# pc_ads1292r_shield_v3_1.net
KiCad netlist of a schematic drawn in EAGLE
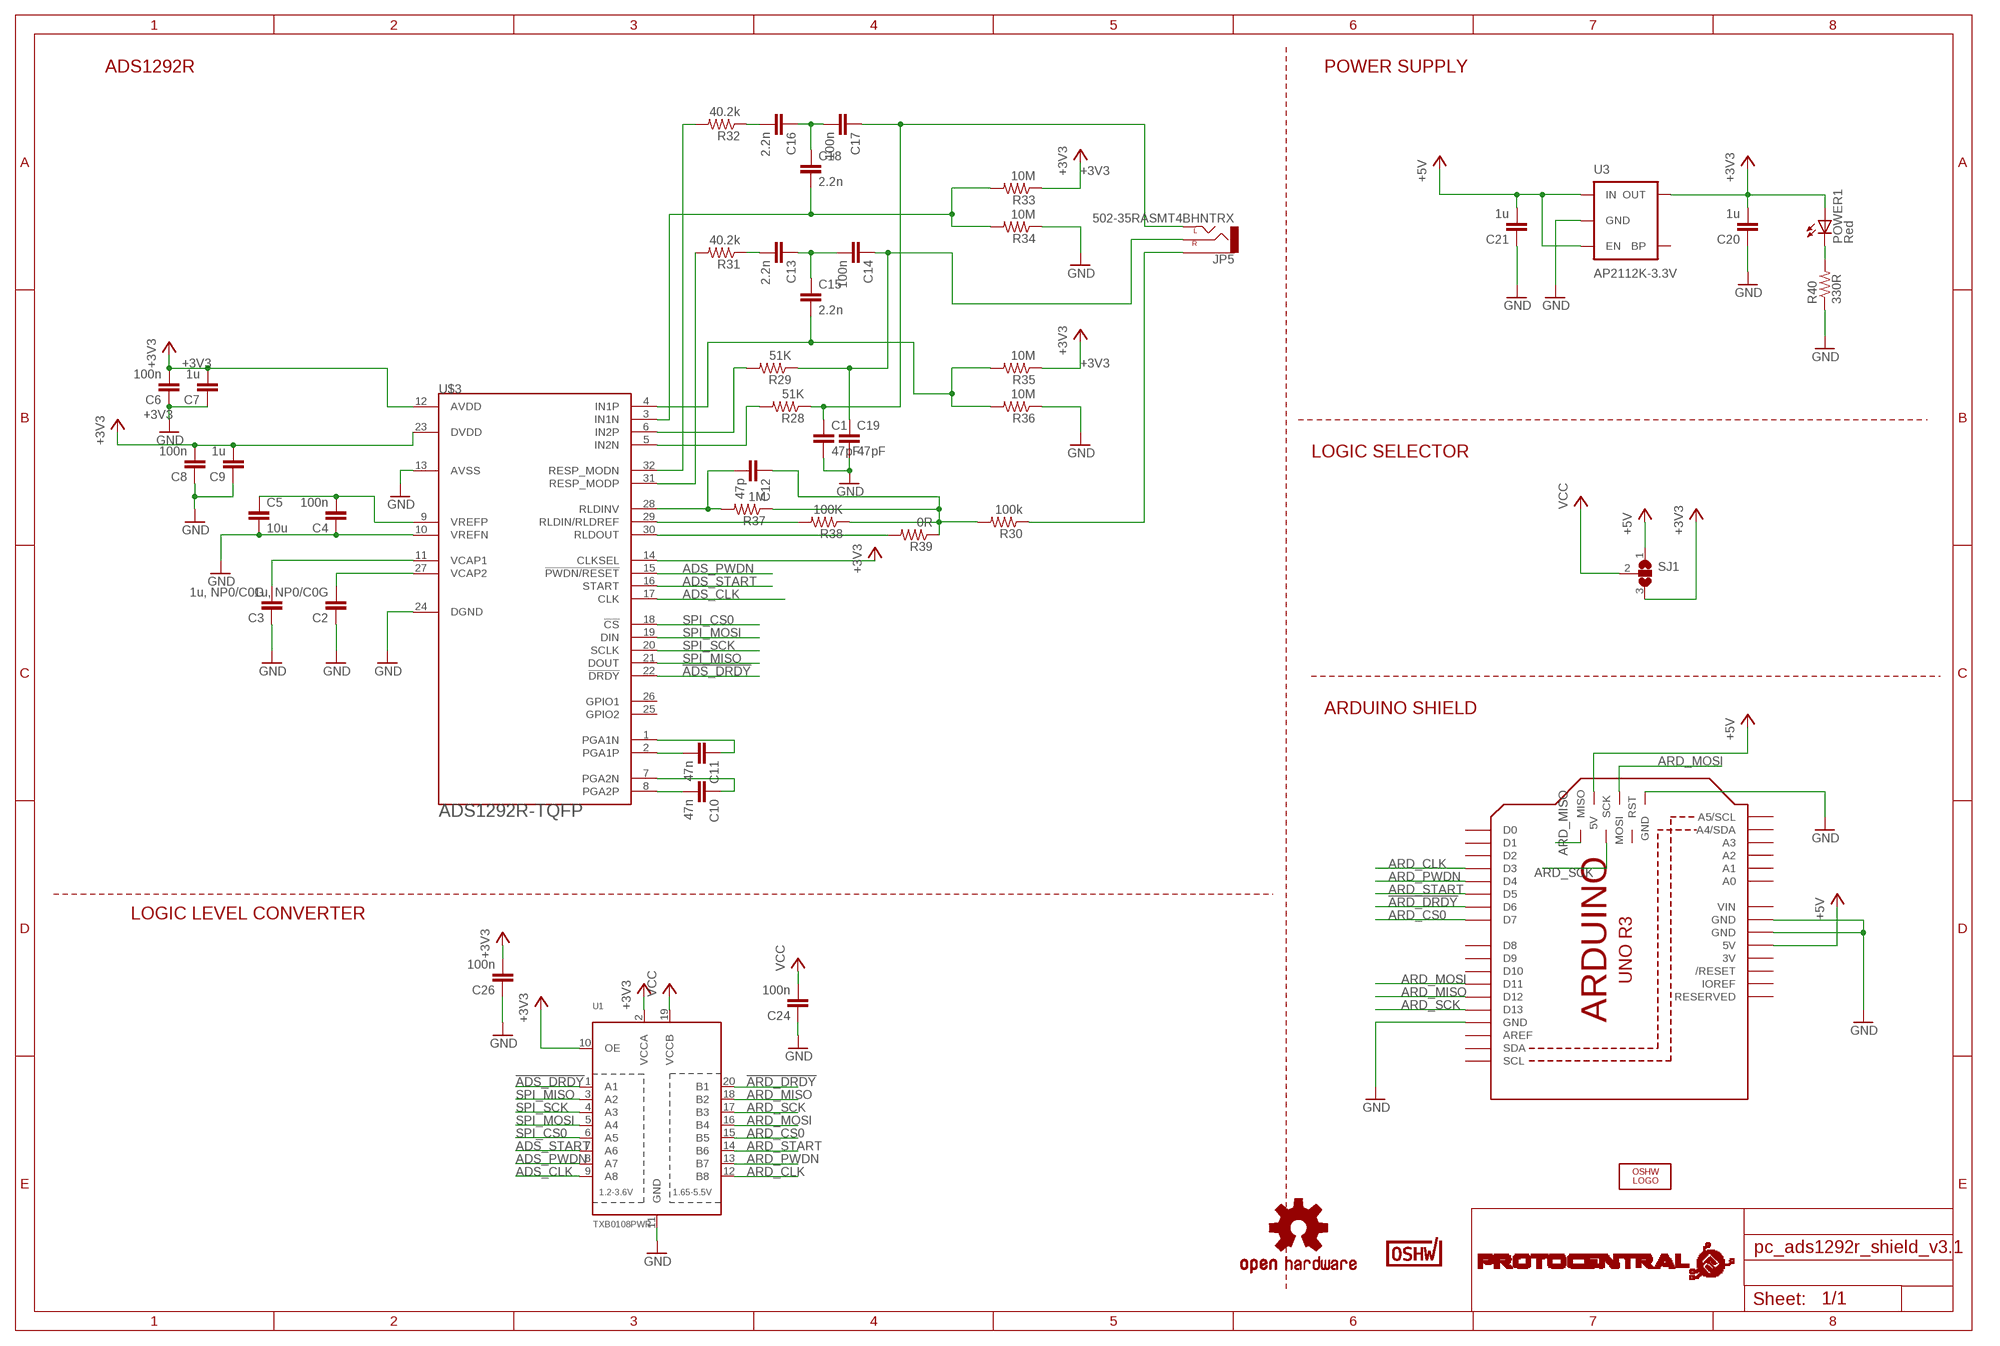
[diagram p0: schematic, sheet 1]

(export (version "E")
  (design (tool "Eeschema 10.0.6"))
  (components
    (comp (ref "C1")
      (value "47pF")
      (footprint "eagle-import:C0402")
      (libsource (lib "eagle-import") (part "C-EUC0402"))
    )
    (comp (ref "C2")
      (value "1u, NP0/C0G")
      (footprint "eagle-import:C0402")
      (libsource (lib "eagle-import") (part "C-EUC0402"))
    )
    (comp (ref "C3")
      (value "1u, NP0/C0G")
      (footprint "eagle-import:C0402")
      (libsource (lib "eagle-import") (part "C-EUC0402"))
    )
    (comp (ref "C4")
      (value "100n")
      (footprint "eagle-import:C0402")
      (libsource (lib "eagle-import") (part "C-EUC0402"))
    )
    (comp (ref "C5")
      (value "10u")
      (footprint "eagle-import:C0603")
      (libsource (lib "eagle-import") (part "resistor_C-EUC0603"))
    )
    (comp (ref "C6")
      (value "100n")
      (footprint "eagle-import:C0402")
      (libsource (lib "eagle-import") (part "C-EUC0402"))
    )
    (comp (ref "C7")
      (value "1u")
      (footprint "eagle-import:C0402")
      (libsource (lib "eagle-import") (part "C-EUC0402"))
    )
    (comp (ref "C8")
      (value "100n")
      (footprint "eagle-import:C0402")
      (libsource (lib "eagle-import") (part "C-EUC0402"))
    )
    (comp (ref "C9")
      (value "1u")
      (footprint "eagle-import:C0402")
      (libsource (lib "eagle-import") (part "C-EUC0402"))
    )
    (comp (ref "C10")
      (value "47n")
      (footprint "eagle-import:C0402")
      (libsource (lib "eagle-import") (part "C-EUC0402"))
    )
    (comp (ref "C11")
      (value "47n")
      (footprint "eagle-import:C0402")
      (libsource (lib "eagle-import") (part "C-EUC0402"))
    )
    (comp (ref "C12")
      (value "47p")
      (footprint "eagle-import:C0402")
      (libsource (lib "eagle-import") (part "C-EUC0402"))
    )
    (comp (ref "C13")
      (value "2.2n")
      (footprint "eagle-import:C0402")
      (libsource (lib "eagle-import") (part "C-EUC0402"))
    )
    (comp (ref "C14")
      (value "100n")
      (footprint "eagle-import:C0402")
      (libsource (lib "eagle-import") (part "C-EUC0402"))
    )
    (comp (ref "C15")
      (value "2.2n")
      (footprint "eagle-import:C0402")
      (libsource (lib "eagle-import") (part "C-EUC0402"))
    )
    (comp (ref "C16")
      (value "2.2n")
      (footprint "eagle-import:C0402")
      (libsource (lib "eagle-import") (part "C-EUC0402"))
    )
    (comp (ref "C17")
      (value "100n")
      (footprint "eagle-import:C0402")
      (libsource (lib "eagle-import") (part "C-EUC0402"))
    )
    (comp (ref "C18")
      (value "2.2n")
      (footprint "eagle-import:C0402")
      (libsource (lib "eagle-import") (part "C-EUC0402"))
    )
    (comp (ref "C19")
      (value "47pF")
      (footprint "eagle-import:C0402")
      (libsource (lib "eagle-import") (part "C-EUC0402"))
    )
    (comp (ref "C20")
      (value "1u")
      (footprint "eagle-import:C0402")
      (libsource (lib "eagle-import") (part "C-EUC0402"))
    )
    (comp (ref "C21")
      (value "1u")
      (footprint "eagle-import:C0402")
      (libsource (lib "eagle-import") (part "C-EUC0402"))
    )
    (comp (ref "C24")
      (value "100n")
      (footprint "eagle-import:C0402")
      (libsource (lib "eagle-import") (part "C-EUC0402"))
    )
    (comp (ref "C26")
      (value "100n")
      (footprint "eagle-import:C0402")
      (libsource (lib "eagle-import") (part "C-EUC0402"))
    )
    (comp (ref "JP5")
      (value "502-35RASMT4BHNTRX")
      (footprint "eagle-import:AUDIO-JACK-3.5MM-SMD")
      (libsource (lib "eagle-import") (part "AUDIO-JACKSMD2"))
    )
    (comp (ref "LOGO1")
      (value "OSHW_LOGO_FILLX0100-NT")
      (footprint "eagle-import:OSHW_FILLX100_NOTEXT")
      (libsource (lib "eagle-import") (part "OSHW_LOGO_FILLX0100-NT"))
    )
    (comp (ref "M1")
      (value "ARDUINO")
      (footprint "eagle-import:ARDUINO")
      (libsource (lib "eagle-import") (part "ARDUINO"))
    )
    (comp (ref "POWER1")
      (value "Red")
      (footprint "eagle-import:CHIPLED_0603")
      (libsource (lib "eagle-import") (part "LEDCHIPLED_0603"))
    )
    (comp (ref "R28")
      (value "51K")
      (footprint "eagle-import:R0402")
      (libsource (lib "eagle-import") (part "R-US_R0402"))
    )
    (comp (ref "R29")
      (value "51K")
      (footprint "eagle-import:R0402")
      (libsource (lib "eagle-import") (part "R-US_R0402"))
    )
    (comp (ref "R30")
      (value "100k")
      (footprint "eagle-import:R0402")
      (libsource (lib "eagle-import") (part "R-US_R0402"))
    )
    (comp (ref "R31")
      (value "40.2k")
      (footprint "eagle-import:R0402")
      (libsource (lib "eagle-import") (part "R-US_R0402"))
    )
    (comp (ref "R32")
      (value "40.2k")
      (footprint "eagle-import:R0402")
      (libsource (lib "eagle-import") (part "R-US_R0402"))
    )
    (comp (ref "R33")
      (value "10M")
      (footprint "eagle-import:R0402")
      (libsource (lib "eagle-import") (part "R-US_R0402"))
    )
    (comp (ref "R34")
      (value "10M")
      (footprint "eagle-import:R0402")
      (libsource (lib "eagle-import") (part "R-US_R0402"))
    )
    (comp (ref "R35")
      (value "10M")
      (footprint "eagle-import:R0402")
      (libsource (lib "eagle-import") (part "R-US_R0402"))
    )
    (comp (ref "R36")
      (value "10M")
      (footprint "eagle-import:R0402")
      (libsource (lib "eagle-import") (part "R-US_R0402"))
    )
    (comp (ref "R37")
      (value "1M")
      (footprint "eagle-import:R0402")
      (libsource (lib "eagle-import") (part "R-US_R0402"))
    )
    (comp (ref "R38")
      (value "100K")
      (footprint "eagle-import:R0402")
      (libsource (lib "eagle-import") (part "R-US_R0402"))
    )
    (comp (ref "R39")
      (value "0R")
      (footprint "eagle-import:R0402")
      (libsource (lib "eagle-import") (part "R-US_R0402"))
    )
    (comp (ref "R40")
      (value "330R")
      (footprint "eagle-import:R0402")
      (libsource (lib "eagle-import") (part "R-US_R0402"))
    )
    (comp (ref "SJ1")
      (value "SJ2W")
      (footprint "eagle-import:SJ_2")
      (libsource (lib "eagle-import") (part "SJ2W"))
    )
    (comp (ref "U$1")
      (value "CERT-SMALL")
      (footprint "eagle-import:CERT-SMALL-SILK")
      (libsource (lib "eagle-import") (part "CERT-SMALL"))
    )
    (comp (ref "U$3")
      (value "ADS1292R-TQFP")
      (footprint "eagle-import:SQFP-S-5X5-32")
      (libsource (lib "eagle-import") (part "ADS1292R-TQFP"))
    )
    (comp (ref "U$4")
      (value "PROTY_LOGO_WITH_TEXT")
      (footprint "eagle-import:PROTY_WITH_TEXT")
      (libsource (lib "eagle-import") (part "PROTY_LOGO_WITH_TEXT"))
    )
    (comp (ref "U$6")
      (value "OSHW-LOGOS")
      (footprint "eagle-import:OSHW-LOGO-S")
      (libsource (lib "eagle-import") (part "OSHW-LOGOS"))
    )
    (comp (ref "U1")
      (value "TXB0108PWR")
      (footprint "eagle-import:TSSOP20")
      (libsource (lib "eagle-import") (part "TXB0108PWR"))
    )
    (comp (ref "U3")
      (value "AP2112K-3.3V")
      (footprint "eagle-import:SOT23-5")
      (libsource (lib "eagle-import") (part "V_REG_LDOSMD"))
    )
  )
  (nets
    (net (code "1") (name "+3V3") (class "Default")
      (node (ref "C20") (pin "2") (pinfunction "2_2") (pintype "passive"))
      (node (ref "C26") (pin "2") (pinfunction "2_2") (pintype "passive"))
      (node (ref "C6") (pin "2") (pinfunction "2_2") (pintype "passive"))
      (node (ref "C7") (pin "2") (pinfunction "2_2") (pintype "passive"))
      (node (ref "C8") (pin "2") (pinfunction "2_2") (pintype "passive"))
      (node (ref "C9") (pin "2") (pinfunction "2_2") (pintype "passive"))
      (node (ref "POWER1") (pin "A") (pinfunction "A_A") (pintype "passive"))
      (node (ref "R33") (pin "1") (pinfunction "1_1") (pintype "passive"))
      (node (ref "R35") (pin "1") (pinfunction "1_1") (pintype "passive"))
      (node (ref "SJ1") (pin "3") (pinfunction "3_3") (pintype "passive"))
      (node (ref "U$3") (pin "12") (pinfunction "AVDD_12") (pintype "power_in"))
      (node (ref "U$3") (pin "14") (pinfunction "CLKSEL_14") (pintype "bidirectional"))
      (node (ref "U$3") (pin "23") (pinfunction "DVDD_23") (pintype "power_in"))
      (node (ref "U1") (pin "10") (pinfunction "OE_10") (pintype "bidirectional"))
      (node (ref "U1") (pin "2") (pinfunction "VCCA_2") (pintype "bidirectional"))
      (node (ref "U3") (pin "5") (pinfunction "OUT_5") (pintype "passive"))
    )
    (net (code "2") (name "+5V") (class "Default")
      (node (ref "C21") (pin "2") (pinfunction "2_2") (pintype "passive"))
      (node (ref "M1") (pin "5V") (pinfunction "5V_5V") (pintype "power_in"))
      (node (ref "M1") (pin "5V_ICSP") (pinfunction "5V_5V_ICSP") (pintype "passive"))
      (node (ref "SJ1") (pin "1") (pinfunction "1_1") (pintype "passive"))
      (node (ref "U3") (pin "1") (pinfunction "IN_1") (pintype "input"))
      (node (ref "U3") (pin "3") (pinfunction "EN_3") (pintype "input"))
    )
    (net (code "3") (name "/3V") (class "Default")
      (node (ref "M1") (pin "3V") (pinfunction "3V_3V") (pintype "power_in"))
    )
    (net (code "4") (name "/ADS_CLK") (class "Default")
      (node (ref "U$3") (pin "17") (pinfunction "CLK_17") (pintype "bidirectional"))
      (node (ref "U1") (pin "9") (pinfunction "A8_9") (pintype "bidirectional"))
    )
    (net (code "5") (name "/ADS_PWDN") (class "Default")
      (node (ref "U$3") (pin "15") (pinfunction "~{PWDN/RESET}_15") (pintype "bidirectional"))
      (node (ref "U1") (pin "8") (pinfunction "A7_8") (pintype "bidirectional"))
    )
    (net (code "6") (name "/ADS_START") (class "Default")
      (node (ref "U$3") (pin "16") (pinfunction "START_16") (pintype "bidirectional"))
      (node (ref "U1") (pin "7") (pinfunction "A6_7") (pintype "bidirectional"))
    )
    (net (code "7") (name "/ARD_CLK") (class "Default")
      (node (ref "M1") (pin "D3") (pinfunction "D3_D3") (pintype "bidirectional"))
      (node (ref "U1") (pin "12") (pinfunction "B8_12") (pintype "bidirectional"))
    )
    (net (code "8") (name "/ARD_CS0") (class "Default")
      (node (ref "M1") (pin "D7") (pinfunction "D7_D7") (pintype "bidirectional"))
      (node (ref "U1") (pin "15") (pinfunction "B5_15") (pintype "bidirectional"))
    )
    (net (code "9") (name "/ARD_MISO") (class "Default")
      (node (ref "M1") (pin "D12") (pinfunction "D12_D12") (pintype "bidirectional"))
      (node (ref "M1") (pin "MISO") (pinfunction "MISO_MISO") (pintype "passive"))
      (node (ref "U1") (pin "18") (pinfunction "B2_18") (pintype "bidirectional"))
    )
    (net (code "10") (name "/ARD_MOSI") (class "Default")
      (node (ref "M1") (pin "D11") (pinfunction "D11_D11") (pintype "bidirectional"))
      (node (ref "M1") (pin "MOSI") (pinfunction "MOSI_MOSI") (pintype "passive"))
      (node (ref "U1") (pin "16") (pinfunction "B4_16") (pintype "bidirectional"))
    )
    (net (code "11") (name "/ARD_PWDN") (class "Default")
      (node (ref "M1") (pin "D4") (pinfunction "D4_D4") (pintype "bidirectional"))
      (node (ref "U1") (pin "13") (pinfunction "B7_13") (pintype "bidirectional"))
    )
    (net (code "12") (name "/ARD_SCK") (class "Default")
      (node (ref "M1") (pin "D13") (pinfunction "D13_D13") (pintype "bidirectional"))
      (node (ref "M1") (pin "SCK") (pinfunction "SCK_SCK") (pintype "passive"))
      (node (ref "U1") (pin "17") (pinfunction "B3_17") (pintype "bidirectional"))
    )
    (net (code "13") (name "/ARD_START") (class "Default")
      (node (ref "M1") (pin "D5") (pinfunction "D5_D5") (pintype "bidirectional"))
      (node (ref "U1") (pin "14") (pinfunction "B6_14") (pintype "bidirectional"))
    )
    (net (code "14") (name "/SPI_CS0") (class "Default")
      (node (ref "U$3") (pin "18") (pinfunction "~{CS}_18") (pintype "bidirectional"))
      (node (ref "U1") (pin "6") (pinfunction "A5_6") (pintype "bidirectional"))
    )
    (net (code "15") (name "/SPI_MISO") (class "Default")
      (node (ref "U$3") (pin "21") (pinfunction "DOUT_21") (pintype "bidirectional"))
      (node (ref "U1") (pin "3") (pinfunction "A2_3") (pintype "bidirectional"))
    )
    (net (code "16") (name "/SPI_MOSI") (class "Default")
      (node (ref "U$3") (pin "19") (pinfunction "DIN_19") (pintype "bidirectional"))
      (node (ref "U1") (pin "5") (pinfunction "A4_5") (pintype "bidirectional"))
    )
    (net (code "17") (name "/SPI_SCK") (class "Default")
      (node (ref "U$3") (pin "20") (pinfunction "SCLK_20") (pintype "bidirectional"))
      (node (ref "U1") (pin "4") (pinfunction "A3_4") (pintype "bidirectional"))
    )
    (net (code "18") (name "/VIN") (class "Default")
      (node (ref "M1") (pin "VIN") (pinfunction "VIN_VIN") (pintype "power_in"))
    )
    (net (code "19") (name "/~{ADS_DRDY}") (class "Default")
      (node (ref "U$3") (pin "22") (pinfunction "~{DRDY}_22") (pintype "bidirectional"))
      (node (ref "U1") (pin "1") (pinfunction "A1_1") (pintype "bidirectional"))
    )
    (net (code "20") (name "/~{ARD_DRDY}") (class "Default")
      (node (ref "M1") (pin "D6") (pinfunction "D6_D6") (pintype "bidirectional"))
      (node (ref "U1") (pin "20") (pinfunction "B1_20") (pintype "bidirectional"))
    )
    (net (code "21") (name "GND") (class "Default")
      (node (ref "C1") (pin "2") (pinfunction "2_2") (pintype "passive"))
      (node (ref "C19") (pin "2") (pinfunction "2_2") (pintype "passive"))
      (node (ref "C2") (pin "1") (pinfunction "1_1") (pintype "passive"))
      (node (ref "C20") (pin "1") (pinfunction "1_1") (pintype "passive"))
      (node (ref "C21") (pin "1") (pinfunction "1_1") (pintype "passive"))
      (node (ref "C24") (pin "1") (pinfunction "1_1") (pintype "passive"))
      (node (ref "C26") (pin "1") (pinfunction "1_1") (pintype "passive"))
      (node (ref "C3") (pin "1") (pinfunction "1_1") (pintype "passive"))
      (node (ref "C4") (pin "1") (pinfunction "1_1") (pintype "passive"))
      (node (ref "C5") (pin "2") (pinfunction "2_2") (pintype "passive"))
      (node (ref "C6") (pin "1") (pinfunction "1_1") (pintype "passive"))
      (node (ref "C7") (pin "1") (pinfunction "1_1") (pintype "passive"))
      (node (ref "C8") (pin "1") (pinfunction "1_1") (pintype "passive"))
      (node (ref "C9") (pin "1") (pinfunction "1_1") (pintype "passive"))
      (node (ref "M1") (pin "GND") (pinfunction "GND_GND") (pintype "power_in"))
      (node (ref "M1") (pin "GND@1") (pinfunction "GND_GND@1") (pintype "power_in"))
      (node (ref "M1") (pin "GND@2") (pinfunction "GND_GND@2") (pintype "power_in"))
      (node (ref "M1") (pin "GND@3") (pinfunction "GND_GND@3") (pintype "passive"))
      (node (ref "R34") (pin "1") (pinfunction "1_1") (pintype "passive"))
      (node (ref "R36") (pin "1") (pinfunction "1_1") (pintype "passive"))
      (node (ref "R40") (pin "1") (pinfunction "1_1") (pintype "passive"))
      (node (ref "U$3") (pin "10") (pinfunction "VREFN_10") (pintype "bidirectional"))
      (node (ref "U$3") (pin "13") (pinfunction "AVSS_13") (pintype "bidirectional"))
      (node (ref "U$3") (pin "24") (pinfunction "DGND_24") (pintype "bidirectional"))
      (node (ref "U1") (pin "11") (pinfunction "GND_11") (pintype "bidirectional"))
      (node (ref "U3") (pin "2") (pinfunction "GND_2") (pintype "input"))
    )
    (net (code "22") (name "Net-(C12-Pad1)") (class "Default")
      (node (ref "C12") (pin "1") (pinfunction "1_1") (pintype "passive"))
      (node (ref "R30") (pin "2") (pinfunction "2_2") (pintype "passive"))
      (node (ref "R37") (pin "1") (pinfunction "1_1") (pintype "passive"))
      (node (ref "R38") (pin "1") (pinfunction "1_1") (pintype "passive"))
      (node (ref "R39") (pin "1") (pinfunction "1_1") (pintype "passive"))
    )
    (net (code "23") (name "Net-(C13-Pad1)") (class "Default")
      (node (ref "C13") (pin "1") (pinfunction "1_1") (pintype "passive"))
      (node (ref "C14") (pin "2") (pinfunction "2_2") (pintype "passive"))
      (node (ref "C15") (pin "1") (pinfunction "1_1") (pintype "passive"))
    )
    (net (code "24") (name "Net-(C13-Pad2)") (class "Default")
      (node (ref "C13") (pin "2") (pinfunction "2_2") (pintype "passive"))
      (node (ref "R31") (pin "1") (pinfunction "1_1") (pintype "passive"))
    )
    (net (code "25") (name "Net-(C16-Pad1)") (class "Default")
      (node (ref "C16") (pin "1") (pinfunction "1_1") (pintype "passive"))
      (node (ref "C17") (pin "2") (pinfunction "2_2") (pintype "passive"))
      (node (ref "C18") (pin "1") (pinfunction "1_1") (pintype "passive"))
    )
    (net (code "26") (name "Net-(C16-Pad2)") (class "Default")
      (node (ref "C16") (pin "2") (pinfunction "2_2") (pintype "passive"))
      (node (ref "R32") (pin "1") (pinfunction "1_1") (pintype "passive"))
    )
    (net (code "27") (name "Net-(JP5-LEFT)") (class "Default")
      (node (ref "C1") (pin "1") (pinfunction "1_1") (pintype "passive"))
      (node (ref "C17") (pin "1") (pinfunction "1_1") (pintype "passive"))
      (node (ref "JP5") (pin "TIP") (pinfunction "LEFT_TIP") (pintype "bidirectional"))
      (node (ref "R28") (pin "1") (pinfunction "1_1") (pintype "passive"))
    )
    (net (code "28") (name "Net-(JP5-PadSLEEVE)") (class "Default")
      (node (ref "JP5") (pin "SLEEVE") (pinfunction "SLEEVE_SLEEVE") (pintype "bidirectional"))
      (node (ref "R30") (pin "1") (pinfunction "1_1") (pintype "passive"))
    )
    (net (code "29") (name "Net-(JP5-RIGHT)") (class "Default")
      (node (ref "C14") (pin "1") (pinfunction "1_1") (pintype "passive"))
      (node (ref "C19") (pin "1") (pinfunction "1_1") (pintype "passive"))
      (node (ref "JP5") (pin "RING") (pinfunction "RIGHT_RING") (pintype "bidirectional"))
      (node (ref "R29") (pin "1") (pinfunction "1_1") (pintype "passive"))
    )
    (net (code "30") (name "Net-(POWER1-PadC)") (class "Default")
      (node (ref "POWER1") (pin "C") (pinfunction "C_C") (pintype "passive"))
      (node (ref "R40") (pin "2") (pinfunction "2_2") (pintype "passive"))
    )
    (net (code "31") (name "Net-(U$3-IN1N)") (class "Default")
      (node (ref "C18") (pin "2") (pinfunction "2_2") (pintype "passive"))
      (node (ref "R33") (pin "2") (pinfunction "2_2") (pintype "passive"))
      (node (ref "R34") (pin "2") (pinfunction "2_2") (pintype "passive"))
      (node (ref "U$3") (pin "3") (pinfunction "IN1N_3") (pintype "input"))
    )
    (net (code "32") (name "Net-(U$3-IN1P)") (class "Default")
      (node (ref "C15") (pin "2") (pinfunction "2_2") (pintype "passive"))
      (node (ref "R35") (pin "2") (pinfunction "2_2") (pintype "passive"))
      (node (ref "R36") (pin "2") (pinfunction "2_2") (pintype "passive"))
      (node (ref "U$3") (pin "4") (pinfunction "IN1P_4") (pintype "input"))
    )
    (net (code "33") (name "Net-(U$3-IN2N)") (class "Default")
      (node (ref "R28") (pin "2") (pinfunction "2_2") (pintype "passive"))
      (node (ref "U$3") (pin "5") (pinfunction "IN2N_5") (pintype "input"))
    )
    (net (code "34") (name "Net-(U$3-IN2P)") (class "Default")
      (node (ref "R29") (pin "2") (pinfunction "2_2") (pintype "passive"))
      (node (ref "U$3") (pin "6") (pinfunction "IN2P_6") (pintype "input"))
    )
    (net (code "35") (name "Net-(U$3-PGA1N)") (class "Default")
      (node (ref "C11") (pin "1") (pinfunction "1_1") (pintype "passive"))
      (node (ref "U$3") (pin "1") (pinfunction "PGA1N_1") (pintype "bidirectional"))
    )
    (net (code "36") (name "Net-(U$3-PGA1P)") (class "Default")
      (node (ref "C11") (pin "2") (pinfunction "2_2") (pintype "passive"))
      (node (ref "U$3") (pin "2") (pinfunction "PGA1P_2") (pintype "bidirectional"))
    )
    (net (code "37") (name "Net-(U$3-PGA2N)") (class "Default")
      (node (ref "C10") (pin "1") (pinfunction "1_1") (pintype "passive"))
      (node (ref "U$3") (pin "7") (pinfunction "PGA2N_7") (pintype "bidirectional"))
    )
    (net (code "38") (name "Net-(U$3-PGA2P)") (class "Default")
      (node (ref "C10") (pin "2") (pinfunction "2_2") (pintype "passive"))
      (node (ref "U$3") (pin "8") (pinfunction "PGA2P_8") (pintype "bidirectional"))
    )
    (net (code "39") (name "Net-(U$3-RESP_MODN)") (class "Default")
      (node (ref "R32") (pin "2") (pinfunction "2_2") (pintype "passive"))
      (node (ref "U$3") (pin "32") (pinfunction "RESP_MODN_32") (pintype "bidirectional"))
    )
    (net (code "40") (name "Net-(U$3-RESP_MODP)") (class "Default")
      (node (ref "R31") (pin "2") (pinfunction "2_2") (pintype "passive"))
      (node (ref "U$3") (pin "31") (pinfunction "RESP_MODP_31") (pintype "bidirectional"))
    )
    (net (code "41") (name "Net-(U$3-RLDINV)") (class "Default")
      (node (ref "C12") (pin "2") (pinfunction "2_2") (pintype "passive"))
      (node (ref "R37") (pin "2") (pinfunction "2_2") (pintype "passive"))
      (node (ref "U$3") (pin "28") (pinfunction "RLDINV_28") (pintype "bidirectional"))
    )
    (net (code "42") (name "Net-(U$3-RLDIN{slash}RLDREF)") (class "Default")
      (node (ref "R38") (pin "2") (pinfunction "2_2") (pintype "passive"))
      (node (ref "U$3") (pin "29") (pinfunction "RLDIN/RLDREF_29") (pintype "bidirectional"))
    )
    (net (code "43") (name "Net-(U$3-RLDOUT)") (class "Default")
      (node (ref "R39") (pin "2") (pinfunction "2_2") (pintype "passive"))
      (node (ref "U$3") (pin "30") (pinfunction "RLDOUT_30") (pintype "bidirectional"))
    )
    (net (code "44") (name "Net-(U$3-VCAP1)") (class "Default")
      (node (ref "C3") (pin "2") (pinfunction "2_2") (pintype "passive"))
      (node (ref "U$3") (pin "11") (pinfunction "VCAP1_11") (pintype "bidirectional"))
    )
    (net (code "45") (name "Net-(U$3-VCAP2)") (class "Default")
      (node (ref "C2") (pin "2") (pinfunction "2_2") (pintype "passive"))
      (node (ref "U$3") (pin "27") (pinfunction "VCAP2_27") (pintype "bidirectional"))
    )
    (net (code "46") (name "Net-(U$3-VREFP)") (class "Default")
      (node (ref "C4") (pin "2") (pinfunction "2_2") (pintype "passive"))
      (node (ref "C5") (pin "1") (pinfunction "1_1") (pintype "passive"))
      (node (ref "U$3") (pin "9") (pinfunction "VREFP_9") (pintype "bidirectional"))
    )
    (net (code "47") (name "VCC") (class "Default")
      (node (ref "C24") (pin "2") (pinfunction "2_2") (pintype "passive"))
      (node (ref "SJ1") (pin "2") (pinfunction "2_2") (pintype "passive"))
      (node (ref "U1") (pin "19") (pinfunction "VCCB_19") (pintype "bidirectional"))
    )
    (net (code "48") (name "unconnected-(M1-A4{slash}SDA-PadA4)") (class "Default")
      (node (ref "M1") (pin "A4") (pinfunction "A4/SDA_A4") (pintype "bidirectional"))
    )
    (net (code "49") (name "unconnected-(M1-A5{slash}SCL-PadA5)") (class "Default")
      (node (ref "M1") (pin "A5") (pinfunction "A5/SCL_A5") (pintype "bidirectional"))
    )
    (net (code "50") (name "unconnected-(M1-PadA0)") (class "Default")
      (node (ref "M1") (pin "A0") (pinfunction "A0_A0") (pintype "bidirectional"))
    )
    (net (code "51") (name "unconnected-(M1-PadA1)") (class "Default")
      (node (ref "M1") (pin "A1") (pinfunction "A1_A1") (pintype "bidirectional"))
    )
    (net (code "52") (name "unconnected-(M1-PadA2)") (class "Default")
      (node (ref "M1") (pin "A2") (pinfunction "A2_A2") (pintype "bidirectional"))
    )
    (net (code "53") (name "unconnected-(M1-PadA3)") (class "Default")
      (node (ref "M1") (pin "A3") (pinfunction "A3_A3") (pintype "bidirectional"))
    )
    (net (code "54") (name "unconnected-(M1-PadAREF)") (class "Default")
      (node (ref "M1") (pin "AREF") (pinfunction "AREF_AREF") (pintype "bidirectional"))
    )
    (net (code "55") (name "unconnected-(M1-PadD0)") (class "Default")
      (node (ref "M1") (pin "D0") (pinfunction "D0_D0") (pintype "bidirectional"))
    )
    (net (code "56") (name "unconnected-(M1-PadD1)") (class "Default")
      (node (ref "M1") (pin "D1") (pinfunction "D1_D1") (pintype "bidirectional"))
    )
    (net (code "57") (name "unconnected-(M1-PadD2)") (class "Default")
      (node (ref "M1") (pin "D2") (pinfunction "D2_D2") (pintype "bidirectional"))
    )
    (net (code "58") (name "unconnected-(M1-PadD8)") (class "Default")
      (node (ref "M1") (pin "D8") (pinfunction "D8_D8") (pintype "bidirectional"))
    )
    (net (code "59") (name "unconnected-(M1-PadD9)") (class "Default")
      (node (ref "M1") (pin "D9") (pinfunction "D9_D9") (pintype "bidirectional"))
    )
    (net (code "60") (name "unconnected-(M1-PadD10)") (class "Default")
      (node (ref "M1") (pin "D10") (pinfunction "D10_D10") (pintype "bidirectional"))
    )
    (net (code "61") (name "unconnected-(M1-PadIOREF)") (class "Default")
      (node (ref "M1") (pin "IOREF") (pinfunction "IOREF_IOREF") (pintype "output"))
    )
    (net (code "62") (name "unconnected-(M1-PadRESERVED)") (class "Default")
      (node (ref "M1") (pin "RESERVED") (pinfunction "RESERVED_RESERVED") (pintype "no_connect"))
    )
    (net (code "63") (name "unconnected-(M1-PadSCL)") (class "Default")
      (node (ref "M1") (pin "SCL") (pinfunction "SCL_SCL") (pintype "bidirectional"))
    )
    (net (code "64") (name "unconnected-(M1-PadSDA)") (class "Default")
      (node (ref "M1") (pin "SDA") (pinfunction "SDA_SDA") (pintype "bidirectional"))
    )
    (net (code "65") (name "unconnected-(M1-RST-PadRESET_ICSP)") (class "Default")
      (node (ref "M1") (pin "RESET_ICSP") (pinfunction "RST_RESET_ICSP") (pintype "passive"))
    )
    (net (code "66") (name "unconnected-(M1-{slash}RESET-PadRESET)") (class "Default")
      (node (ref "M1") (pin "RESET") (pinfunction "/RESET_RESET") (pintype "bidirectional"))
    )
    (net (code "67") (name "unconnected-(U$3-GPIO1-Pad26)") (class "Default")
      (node (ref "U$3") (pin "26") (pinfunction "GPIO1_26") (pintype "bidirectional"))
    )
    (net (code "68") (name "unconnected-(U$3-GPIO2-Pad25)") (class "Default")
      (node (ref "U$3") (pin "25") (pinfunction "GPIO2_25") (pintype "bidirectional"))
    )
    (net (code "69") (name "unconnected-(U3-BP-Pad4)") (class "Default")
      (node (ref "U3") (pin "4") (pinfunction "BP_4") (pintype "input"))
    )
  )
)
